# ADC-POWER_SUPPLY.net
KiCad netlist of a schematic drawn in Altium Designer
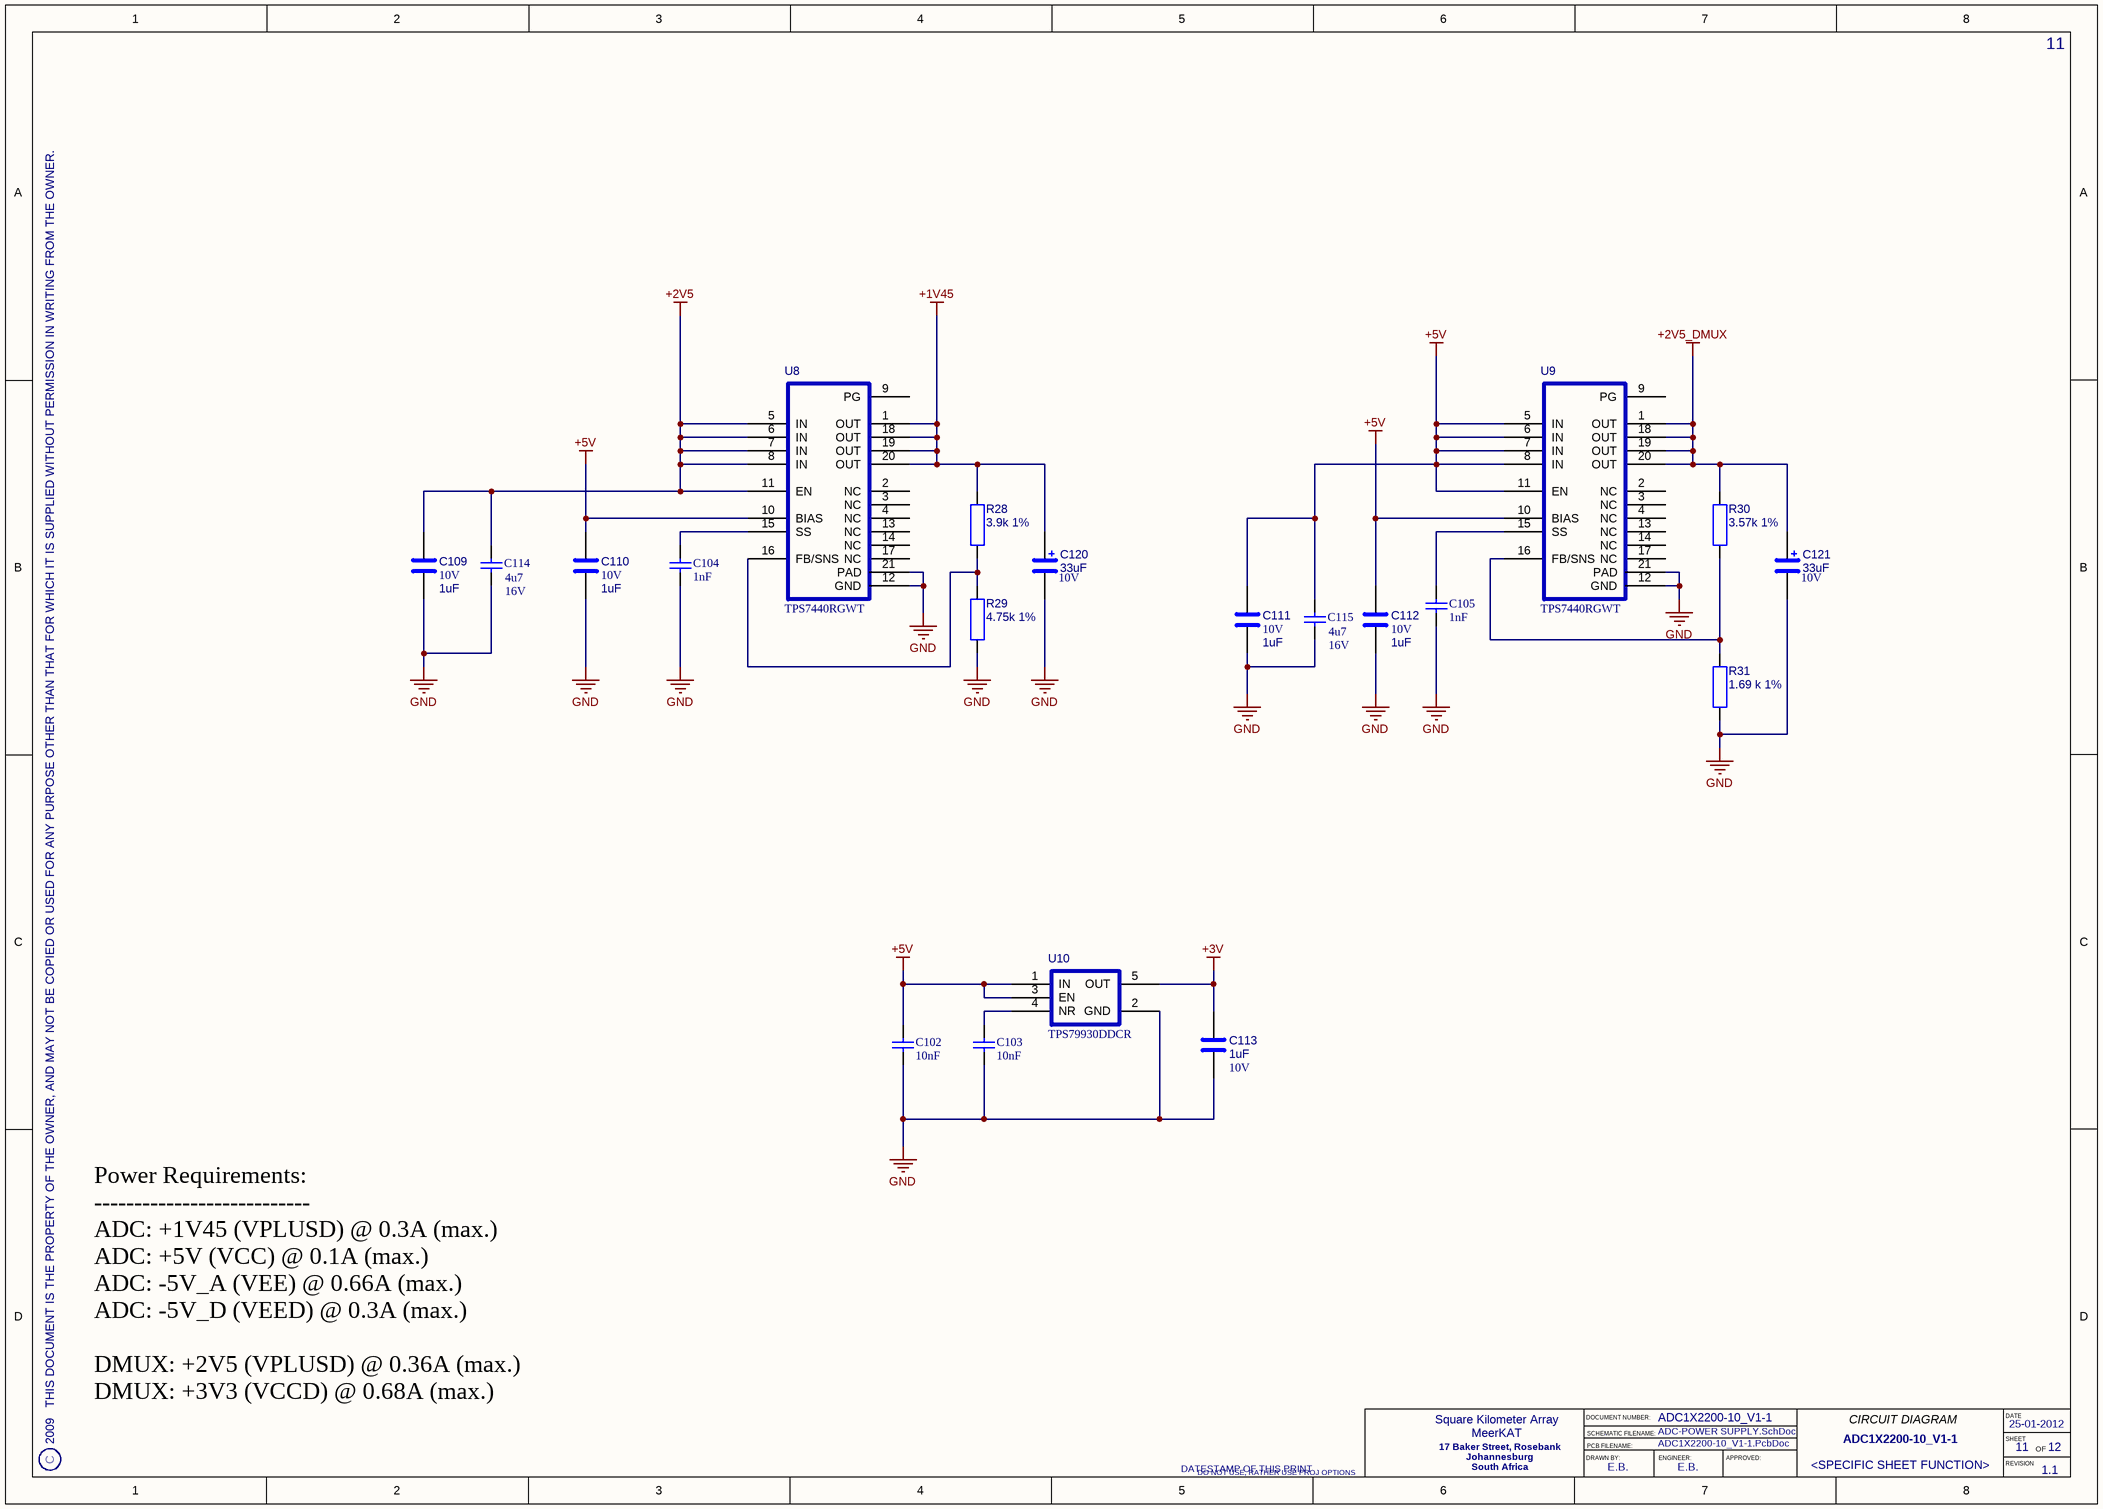
[diagram p0: ADC-POWER SUPPLY.SchDoc]

(export (version "E")
  (design (tool "Eeschema 10.0.6"))
  (components
    (comp (ref "C102")
      (value "10nF")
      (footprint "CAPC1005X55N")
      (description "Capacitor 0402 SMD")
      (fields (field (name "CREATED_BY") "EDA-ASA") (field (name "CHECKED_BY") "*"))
      (libsource (lib "EDA-Passive") (part "cap0402"))
    )
    (comp (ref "C103")
      (value "10nF")
      (footprint "CAPC1005X55N")
      (description "Capacitor 0402 SMD")
      (fields (field (name "CREATED_BY") "EDA-ASA") (field (name "CHECKED_BY") "*"))
      (libsource (lib "EDA-Passive") (part "cap0402"))
    )
    (comp (ref "C104")
      (value "1nF")
      (footprint "CAPC1005X55N")
      (description "Capacitor 0402 SMD")
      (fields (field (name "CREATED_BY") "EDA-ASA") (field (name "CHECKED_BY") "*"))
      (libsource (lib "EDA-Passive") (part "cap0402"))
    )
    (comp (ref "C105")
      (value "1nF")
      (footprint "CAPC1005X55N")
      (description "Capacitor 0402 SMD")
      (fields (field (name "CREATED_BY") "EDA-ASA") (field (name "CHECKED_BY") "*"))
      (libsource (lib "EDA-Passive") (part "cap0402"))
    )
    (comp (ref "C109")
      (value "1uF")
      (footprint "CAPC1632X80USR")
      (description "CAP SMD 1206")
      (fields (field (name "VOLTAGE") "10V") (field (name "CREATED_BY") "*") (field (name "CHECKED_BY") "*"))
      (libsource (lib "Abdus-TEMP") (part "CAP-0603"))
    )
    (comp (ref "C110")
      (value "1uF")
      (footprint "CAPC1632X80USR")
      (description "CAP SMD 1206")
      (fields (field (name "VOLTAGE") "10V") (field (name "CREATED_BY") "*") (field (name "CHECKED_BY") "*"))
      (libsource (lib "Abdus-TEMP") (part "CAP-0603"))
    )
    (comp (ref "C111")
      (value "1uF")
      (footprint "CAPC1632X80USR")
      (description "CAP SMD 1206")
      (fields (field (name "VOLTAGE") "10V") (field (name "CREATED_BY") "*") (field (name "CHECKED_BY") "*"))
      (libsource (lib "Abdus-TEMP") (part "CAP-0603"))
    )
    (comp (ref "C112")
      (value "1uF")
      (footprint "CAPC1632X80USR")
      (description "CAP SMD 1206")
      (fields (field (name "VOLTAGE") "10V") (field (name "CREATED_BY") "*") (field (name "CHECKED_BY") "*"))
      (libsource (lib "Abdus-TEMP") (part "CAP-0603"))
    )
    (comp (ref "C113")
      (value "1uF")
      (footprint "CAPC1632X80USR")
      (description "CAP SMD 1206")
      (fields (field (name "VOLTAGE") "10V") (field (name "CREATED_BY") "*") (field (name "CHECKED_BY") "*"))
      (libsource (lib "Abdus-TEMP") (part "CAP-0603"))
    )
    (comp (ref "C114")
      (value "4u7")
      (footprint "CAPC3225X220N")
      (description "Capacitor 1210 SMD")
      (fields
        (field (name "VOLTAGE") "16V")
        (field (name "CREATED_BY") "EDA-ASA")
        (field (name "CHECKED_BY") "*")
      )
      (libsource (lib "EDA-Passive") (part "cap1210"))
    )
    (comp (ref "C115")
      (value "4u7")
      (footprint "CAPC3225X220N")
      (description "Capacitor 1210 SMD")
      (fields
        (field (name "VOLTAGE") "16V")
        (field (name "CREATED_BY") "EDA-ASA")
        (field (name "CHECKED_BY") "*")
      )
      (libsource (lib "EDA-Passive") (part "cap1210"))
    )
    (comp (ref "C120")
      (value "33uF")
      (footprint "3528")
      (description "CAPACITOR-POLARISED")
      (fields
        (field (name "VOLTAGE") "10V")
        (field (name "CREATED_BY") "EDA-ASA")
        (field (name "CHECKED_BY") "*")
      )
      (libsource (lib "EDA_GenericSymbols") (part "CAPACITOR-POLARISED"))
    )
    (comp (ref "C121")
      (value "33uF")
      (footprint "3528")
      (description "CAPACITOR-POLARISED")
      (fields
        (field (name "VOLTAGE") "10V")
        (field (name "CREATED_BY") "EDA-ASA")
        (field (name "CHECKED_BY") "*")
      )
      (libsource (lib "EDA_GenericSymbols") (part "CAPACITOR-POLARISED"))
    )
    (comp (ref "R28")
      (value "3.9k 1%")
      (footprint "0603")
      (description "RESISTOR SMD 0603")
      (fields (field (name "CREATED_BY") "*") (field (name "CHECKED_BY") "NN"))
      (libsource (lib "EDA_Passive") (part "RES-0805"))
    )
    (comp (ref "R29")
      (value "4.75k 1%")
      (footprint "0603")
      (description "RESISTOR SMD 0603")
      (fields (field (name "CREATED_BY") "*") (field (name "CHECKED_BY") "NN"))
      (libsource (lib "EDA_Passive") (part "RES-0805"))
    )
    (comp (ref "R30")
      (value "3.57k 1%")
      (footprint "0603")
      (description "RESISTOR SMD 0603")
      (fields (field (name "CREATED_BY") "*") (field (name "CHECKED_BY") "NN"))
      (libsource (lib "EDA_Passive") (part "RES-0805"))
    )
    (comp (ref "R31")
      (value "1.69 k 1%")
      (footprint "0603")
      (description "RESISTOR SMD 0603")
      (fields (field (name "CREATED_BY") "*") (field (name "CHECKED_BY") "NN"))
      (libsource (lib "EDA_Passive") (part "RES-0805"))
    )
    (comp (ref "U8")
      (value "TPS7440RGWT")
      (footprint "QFN65P500X500X100-21AN")
      (description "3.0A Ultra-LDO with Programmable Soft-Start")
      (fields
        (field (name "MANUFACTURER") "TI")
        (field (name "CREATED_BY") "IN")
        (field (name "CHECKED_BY") "*")
      )
      (libsource (lib "Ishvah-TEMP") (part "TPS74401RGWT"))
    )
    (comp (ref "U9")
      (value "TPS7440RGWT")
      (footprint "QFN65P500X500X100-21AN")
      (description "3.0A Ultra-LDO with Programmable Soft-Start")
      (fields
        (field (name "MANUFACTURER") "TI")
        (field (name "CREATED_BY") "IN")
        (field (name "CHECKED_BY") "*")
      )
      (libsource (lib "Ishvah-TEMP") (part "TPS74401RGWT"))
    )
    (comp (ref "U10")
      (value "TPS79930DDCR")
      (footprint "SOT95P280X110-5USR2")
      (description "Low Quiescent Current, Ultra-Low Noise Dropout Linear Regulator")
      (fields
        (field (name "MANUFACTURER") "TI")
        (field (name "CREATED_BY") "IN")
        (field (name "CHECKED_BY") "*")
      )
      (libsource (lib "Ishvah-TEMP") (part "TPS7994DDCR"))
    )
  )
  (nets
    (net (code "1") (name "+1V45") (class "Default")
      (node (ref "C120") (pin "1") (pinfunction "1_1") (pintype "passive"))
      (node (ref "R28") (pin "1") (pinfunction "1_1") (pintype "passive"))
      (node (ref "U8") (pin "1") (pinfunction "OUT_1") (pintype "passive"))
      (node (ref "U8") (pin "18") (pinfunction "OUT_18") (pintype "passive"))
      (node (ref "U8") (pin "19") (pinfunction "OUT_19") (pintype "passive"))
      (node (ref "U8") (pin "20") (pinfunction "OUT_20") (pintype "passive"))
    )
    (net (code "2") (name "+2V5") (class "Default")
      (node (ref "C109") (pin "1") (pinfunction "1_1") (pintype "passive"))
      (node (ref "C114") (pin "2") (pinfunction "2_2") (pintype "passive"))
      (node (ref "U8") (pin "11") (pinfunction "EN_11") (pintype "passive"))
      (node (ref "U8") (pin "5") (pinfunction "IN_5") (pintype "passive"))
      (node (ref "U8") (pin "6") (pinfunction "IN_6") (pintype "passive"))
      (node (ref "U8") (pin "7") (pinfunction "IN_7") (pintype "passive"))
      (node (ref "U8") (pin "8") (pinfunction "IN_8") (pintype "passive"))
    )
    (net (code "3") (name "+2V5_DMUX") (class "Default")
      (node (ref "C121") (pin "1") (pinfunction "1_1") (pintype "passive"))
      (node (ref "R30") (pin "1") (pinfunction "1_1") (pintype "passive"))
      (node (ref "U9") (pin "1") (pinfunction "OUT_1") (pintype "passive"))
      (node (ref "U9") (pin "18") (pinfunction "OUT_18") (pintype "passive"))
      (node (ref "U9") (pin "19") (pinfunction "OUT_19") (pintype "passive"))
      (node (ref "U9") (pin "20") (pinfunction "OUT_20") (pintype "passive"))
    )
    (net (code "4") (name "+3V") (class "Default")
      (node (ref "C113") (pin "1") (pinfunction "1_1") (pintype "passive"))
      (node (ref "U10") (pin "5") (pinfunction "OUT_5") (pintype "passive"))
    )
    (net (code "5") (name "+5V") (class "Default")
      (node (ref "C102") (pin "1") (pinfunction "1_1") (pintype "passive"))
      (node (ref "C110") (pin "1") (pinfunction "1_1") (pintype "passive"))
      (node (ref "C111") (pin "1") (pinfunction "1_1") (pintype "passive"))
      (node (ref "C112") (pin "1") (pinfunction "1_1") (pintype "passive"))
      (node (ref "C115") (pin "2") (pinfunction "2_2") (pintype "passive"))
      (node (ref "U10") (pin "1") (pinfunction "IN_1") (pintype "passive"))
      (node (ref "U10") (pin "3") (pinfunction "EN_3") (pintype "passive"))
      (node (ref "U8") (pin "10") (pinfunction "BIAS_10") (pintype "passive"))
      (node (ref "U9") (pin "10") (pinfunction "BIAS_10") (pintype "passive"))
      (node (ref "U9") (pin "11") (pinfunction "EN_11") (pintype "passive"))
      (node (ref "U9") (pin "5") (pinfunction "IN_5") (pintype "passive"))
      (node (ref "U9") (pin "6") (pinfunction "IN_6") (pintype "passive"))
      (node (ref "U9") (pin "7") (pinfunction "IN_7") (pintype "passive"))
      (node (ref "U9") (pin "8") (pinfunction "IN_8") (pintype "passive"))
    )
    (net (code "6") (name "GND") (class "Default")
      (node (ref "C102") (pin "2") (pinfunction "2_2") (pintype "passive"))
      (node (ref "C103") (pin "2") (pinfunction "2_2") (pintype "passive"))
      (node (ref "C104") (pin "1") (pinfunction "1_1") (pintype "passive"))
      (node (ref "C105") (pin "1") (pinfunction "1_1") (pintype "passive"))
      (node (ref "C109") (pin "2") (pinfunction "2_2") (pintype "passive"))
      (node (ref "C110") (pin "2") (pinfunction "2_2") (pintype "passive"))
      (node (ref "C111") (pin "2") (pinfunction "2_2") (pintype "passive"))
      (node (ref "C112") (pin "2") (pinfunction "2_2") (pintype "passive"))
      (node (ref "C113") (pin "2") (pinfunction "2_2") (pintype "passive"))
      (node (ref "C114") (pin "1") (pinfunction "1_1") (pintype "passive"))
      (node (ref "C115") (pin "1") (pinfunction "1_1") (pintype "passive"))
      (node (ref "C120") (pin "2") (pinfunction "2_2") (pintype "passive"))
      (node (ref "C121") (pin "2") (pinfunction "2_2") (pintype "passive"))
      (node (ref "R29") (pin "1") (pinfunction "1_1") (pintype "passive"))
      (node (ref "R31") (pin "1") (pinfunction "1_1") (pintype "passive"))
      (node (ref "U10") (pin "2") (pinfunction "GND_2") (pintype "passive"))
      (node (ref "U8") (pin "12") (pinfunction "GND_12") (pintype "passive"))
      (node (ref "U8") (pin "21") (pinfunction "PAD_21") (pintype "passive"))
      (node (ref "U9") (pin "12") (pinfunction "GND_12") (pintype "passive"))
      (node (ref "U9") (pin "21") (pinfunction "PAD_21") (pintype "passive"))
    )
    (net (code "7") (name "Net-(U8-FB{slash}SNS)") (class "Default")
      (node (ref "R28") (pin "2") (pinfunction "2_2") (pintype "passive"))
      (node (ref "R29") (pin "2") (pinfunction "2_2") (pintype "passive"))
      (node (ref "U8") (pin "16") (pinfunction "FB/SNS_16") (pintype "passive"))
    )
    (net (code "8") (name "Net-(U8-SS)") (class "Default")
      (node (ref "C104") (pin "2") (pinfunction "2_2") (pintype "passive"))
      (node (ref "U8") (pin "15") (pinfunction "SS_15") (pintype "passive"))
    )
    (net (code "9") (name "Net-(U9-FB{slash}SNS)") (class "Default")
      (node (ref "R30") (pin "2") (pinfunction "2_2") (pintype "passive"))
      (node (ref "R31") (pin "2") (pinfunction "2_2") (pintype "passive"))
      (node (ref "U9") (pin "16") (pinfunction "FB/SNS_16") (pintype "passive"))
    )
    (net (code "10") (name "Net-(U9-SS)") (class "Default")
      (node (ref "C105") (pin "2") (pinfunction "2_2") (pintype "passive"))
      (node (ref "U9") (pin "15") (pinfunction "SS_15") (pintype "passive"))
    )
    (net (code "11") (name "Net-(U10-NR)") (class "Default")
      (node (ref "C103") (pin "1") (pinfunction "1_1") (pintype "passive"))
      (node (ref "U10") (pin "4") (pinfunction "NR_4") (pintype "passive"))
    )
    (net (code "12") (name "unconnected-(U8-NC-Pad2)") (class "Default")
      (node (ref "U8") (pin "2") (pinfunction "NC_2") (pintype "passive"))
    )
    (net (code "13") (name "unconnected-(U8-NC-Pad3)") (class "Default")
      (node (ref "U8") (pin "3") (pinfunction "NC_3") (pintype "passive"))
    )
    (net (code "14") (name "unconnected-(U8-NC-Pad4)") (class "Default")
      (node (ref "U8") (pin "4") (pinfunction "NC_4") (pintype "passive"))
    )
    (net (code "15") (name "unconnected-(U8-NC-Pad13)") (class "Default")
      (node (ref "U8") (pin "13") (pinfunction "NC_13") (pintype "passive"))
    )
    (net (code "16") (name "unconnected-(U8-NC-Pad14)") (class "Default")
      (node (ref "U8") (pin "14") (pinfunction "NC_14") (pintype "passive"))
    )
    (net (code "17") (name "unconnected-(U8-NC-Pad17)") (class "Default")
      (node (ref "U8") (pin "17") (pinfunction "NC_17") (pintype "passive"))
    )
    (net (code "18") (name "unconnected-(U8-PG-Pad9)") (class "Default")
      (node (ref "U8") (pin "9") (pinfunction "PG_9") (pintype "passive"))
    )
    (net (code "19") (name "unconnected-(U9-NC-Pad2)") (class "Default")
      (node (ref "U9") (pin "2") (pinfunction "NC_2") (pintype "passive"))
    )
    (net (code "20") (name "unconnected-(U9-NC-Pad3)") (class "Default")
      (node (ref "U9") (pin "3") (pinfunction "NC_3") (pintype "passive"))
    )
    (net (code "21") (name "unconnected-(U9-NC-Pad4)") (class "Default")
      (node (ref "U9") (pin "4") (pinfunction "NC_4") (pintype "passive"))
    )
    (net (code "22") (name "unconnected-(U9-NC-Pad13)") (class "Default")
      (node (ref "U9") (pin "13") (pinfunction "NC_13") (pintype "passive"))
    )
    (net (code "23") (name "unconnected-(U9-NC-Pad14)") (class "Default")
      (node (ref "U9") (pin "14") (pinfunction "NC_14") (pintype "passive"))
    )
    (net (code "24") (name "unconnected-(U9-NC-Pad17)") (class "Default")
      (node (ref "U9") (pin "17") (pinfunction "NC_17") (pintype "passive"))
    )
    (net (code "25") (name "unconnected-(U9-PG-Pad9)") (class "Default")
      (node (ref "U9") (pin "9") (pinfunction "PG_9") (pintype "passive"))
    )
  )
)
